# covox.net
KiCad netlist of a schematic drawn in EAGLE
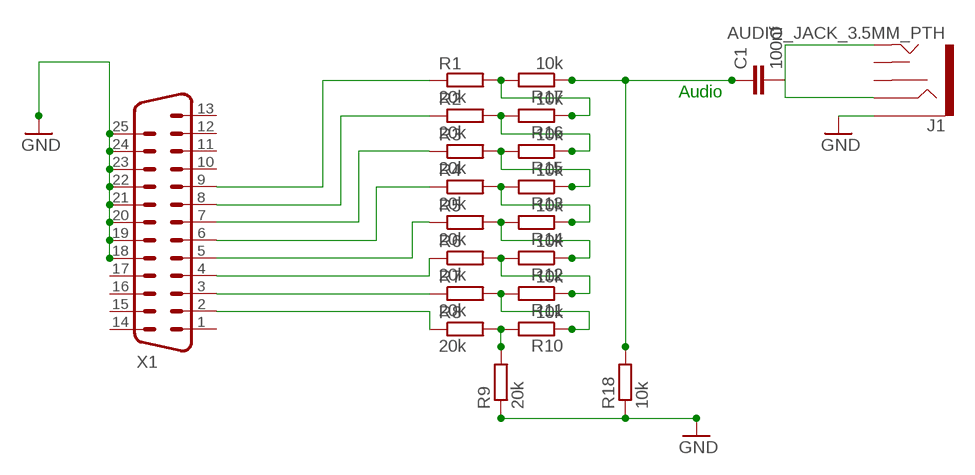
[diagram p0: schematic, sheet 1]

(export (version "E")
  (design (tool "Eeschema 10.0.6"))
  (components
    (comp (ref "C1")
      (value "100nf")
      (footprint "eagle-import:C2.5-2")
      (libsource (lib "eagle-import") (part "C2.5/2"))
    )
    (comp (ref "J1")
      (value "AUDIO_JACK_3.5MM_PTH")
      (footprint "eagle-import:AUDIO-JACK")
      (libsource (lib "eagle-import") (part "AUDIO_JACK_3.5MM_PTH"))
    )
    (comp (ref "R1")
      (value "20k")
      (footprint "eagle-import:0204_7")
      (libsource (lib "eagle-import") (part "R-EU_0204/7"))
    )
    (comp (ref "R2")
      (value "20k")
      (footprint "eagle-import:0204_7")
      (libsource (lib "eagle-import") (part "R-EU_0204/7"))
    )
    (comp (ref "R3")
      (value "20k")
      (footprint "eagle-import:0204_7")
      (libsource (lib "eagle-import") (part "R-EU_0204/7"))
    )
    (comp (ref "R4")
      (value "20k")
      (footprint "eagle-import:0204_7")
      (libsource (lib "eagle-import") (part "R-EU_0204/7"))
    )
    (comp (ref "R5")
      (value "20k")
      (footprint "eagle-import:0204_7")
      (libsource (lib "eagle-import") (part "R-EU_0204/7"))
    )
    (comp (ref "R6")
      (value "20k")
      (footprint "eagle-import:0204_7")
      (libsource (lib "eagle-import") (part "R-EU_0204/7"))
    )
    (comp (ref "R7")
      (value "20k")
      (footprint "eagle-import:0204_7")
      (libsource (lib "eagle-import") (part "R-EU_0204/7"))
    )
    (comp (ref "R8")
      (value "20k")
      (footprint "eagle-import:0204_7")
      (libsource (lib "eagle-import") (part "R-EU_0204/7"))
    )
    (comp (ref "R9")
      (value "20k")
      (footprint "eagle-import:0204_7")
      (libsource (lib "eagle-import") (part "R-EU_0204/7"))
    )
    (comp (ref "R10")
      (value "10k")
      (footprint "eagle-import:0204_7")
      (libsource (lib "eagle-import") (part "R-EU_0204/7"))
    )
    (comp (ref "R11")
      (value "10k")
      (footprint "eagle-import:0204_7")
      (libsource (lib "eagle-import") (part "R-EU_0204/7"))
    )
    (comp (ref "R12")
      (value "10k")
      (footprint "eagle-import:0204_7")
      (libsource (lib "eagle-import") (part "R-EU_0204/7"))
    )
    (comp (ref "R13")
      (value "10k")
      (footprint "eagle-import:0204_7")
      (libsource (lib "eagle-import") (part "R-EU_0204/7"))
    )
    (comp (ref "R14")
      (value "10k")
      (footprint "eagle-import:0204_7")
      (libsource (lib "eagle-import") (part "R-EU_0204/7"))
    )
    (comp (ref "R15")
      (value "10k")
      (footprint "eagle-import:0204_7")
      (libsource (lib "eagle-import") (part "R-EU_0204/7"))
    )
    (comp (ref "R16")
      (value "10k")
      (footprint "eagle-import:0204_7")
      (libsource (lib "eagle-import") (part "R-EU_0204/7"))
    )
    (comp (ref "R17")
      (value "10k")
      (footprint "eagle-import:0204_7")
      (libsource (lib "eagle-import") (part "R-EU_0204/7"))
    )
    (comp (ref "R18")
      (value "10k")
      (footprint "eagle-import:0204_7")
      (libsource (lib "eagle-import") (part "R-EU_0204/7"))
    )
    (comp (ref "X1")
      (value "M25HP")
      (footprint "eagle-import:M25HP")
      (libsource (lib "eagle-import") (part "M25HP"))
    )
  )
  (nets
    (net (code "1") (name "GND") (class "Default")
      (node (ref "J1") (pin "SLEEVE") (pinfunction "SLEEVE_SLEEVE") (pintype "bidirectional"))
      (node (ref "R18") (pin "1") (pinfunction "1_1") (pintype "passive"))
      (node (ref "R9") (pin "1") (pinfunction "1_1") (pintype "passive"))
      (node (ref "X1") (pin "18") (pinfunction "18_18") (pintype "passive"))
      (node (ref "X1") (pin "19") (pinfunction "19_19") (pintype "passive"))
      (node (ref "X1") (pin "20") (pinfunction "20_20") (pintype "passive"))
      (node (ref "X1") (pin "21") (pinfunction "21_21") (pintype "passive"))
      (node (ref "X1") (pin "22") (pinfunction "22_22") (pintype "passive"))
      (node (ref "X1") (pin "23") (pinfunction "23_23") (pintype "passive"))
      (node (ref "X1") (pin "24") (pinfunction "24_24") (pintype "passive"))
      (node (ref "X1") (pin "25") (pinfunction "25_25") (pintype "passive"))
    )
    (net (code "2") (name "Net-(C1-Pad1)") (class "Default")
      (node (ref "C1") (pin "1") (pinfunction "1_1") (pintype "passive"))
      (node (ref "R17") (pin "1") (pinfunction "1_1") (pintype "passive"))
      (node (ref "R18") (pin "2") (pinfunction "2_2") (pintype "passive"))
    )
    (net (code "3") (name "Net-(C1-Pad2)") (class "Default")
      (node (ref "C1") (pin "2") (pinfunction "2_2") (pintype "passive"))
      (node (ref "J1") (pin "RING") (pinfunction "RING_RING") (pintype "bidirectional"))
      (node (ref "J1") (pin "TIP") (pinfunction "TIP_TIP") (pintype "bidirectional"))
    )
    (net (code "4") (name "Net-(R1-Pad1)") (class "Default")
      (node (ref "R1") (pin "1") (pinfunction "1_1") (pintype "passive"))
      (node (ref "X1") (pin "9") (pinfunction "9_9") (pintype "passive"))
    )
    (net (code "5") (name "Net-(R1-Pad2)") (class "Default")
      (node (ref "R1") (pin "2") (pinfunction "2_2") (pintype "passive"))
      (node (ref "R16") (pin "1") (pinfunction "1_1") (pintype "passive"))
      (node (ref "R17") (pin "2") (pinfunction "2_2") (pintype "passive"))
    )
    (net (code "6") (name "Net-(R2-Pad1)") (class "Default")
      (node (ref "R2") (pin "1") (pinfunction "1_1") (pintype "passive"))
      (node (ref "X1") (pin "8") (pinfunction "8_8") (pintype "passive"))
    )
    (net (code "7") (name "Net-(R3-Pad1)") (class "Default")
      (node (ref "R3") (pin "1") (pinfunction "1_1") (pintype "passive"))
      (node (ref "X1") (pin "7") (pinfunction "7_7") (pintype "passive"))
    )
    (net (code "8") (name "Net-(R4-Pad1)") (class "Default")
      (node (ref "R4") (pin "1") (pinfunction "1_1") (pintype "passive"))
      (node (ref "X1") (pin "6") (pinfunction "6_6") (pintype "passive"))
    )
    (net (code "9") (name "Net-(R5-Pad1)") (class "Default")
      (node (ref "R5") (pin "1") (pinfunction "1_1") (pintype "passive"))
      (node (ref "X1") (pin "5") (pinfunction "5_5") (pintype "passive"))
    )
    (net (code "10") (name "Net-(R6-Pad1)") (class "Default")
      (node (ref "R6") (pin "1") (pinfunction "1_1") (pintype "passive"))
      (node (ref "X1") (pin "4") (pinfunction "4_4") (pintype "passive"))
    )
    (net (code "11") (name "Net-(R7-Pad1)") (class "Default")
      (node (ref "R7") (pin "1") (pinfunction "1_1") (pintype "passive"))
      (node (ref "X1") (pin "3") (pinfunction "3_3") (pintype "passive"))
    )
    (net (code "12") (name "Net-(R8-Pad1)") (class "Default")
      (node (ref "R8") (pin "1") (pinfunction "1_1") (pintype "passive"))
      (node (ref "X1") (pin "2") (pinfunction "2_2") (pintype "passive"))
    )
    (net (code "13") (name "Net-(R10-Pad1)") (class "Default")
      (node (ref "R10") (pin "1") (pinfunction "1_1") (pintype "passive"))
      (node (ref "R11") (pin "2") (pinfunction "2_2") (pintype "passive"))
      (node (ref "R7") (pin "2") (pinfunction "2_2") (pintype "passive"))
    )
    (net (code "14") (name "Net-(R10-Pad2)") (class "Default")
      (node (ref "R10") (pin "2") (pinfunction "2_2") (pintype "passive"))
      (node (ref "R8") (pin "2") (pinfunction "2_2") (pintype "passive"))
      (node (ref "R9") (pin "2") (pinfunction "2_2") (pintype "passive"))
    )
    (net (code "15") (name "Net-(R11-Pad1)") (class "Default")
      (node (ref "R11") (pin "1") (pinfunction "1_1") (pintype "passive"))
      (node (ref "R12") (pin "2") (pinfunction "2_2") (pintype "passive"))
      (node (ref "R6") (pin "2") (pinfunction "2_2") (pintype "passive"))
    )
    (net (code "16") (name "Net-(R12-Pad1)") (class "Default")
      (node (ref "R12") (pin "1") (pinfunction "1_1") (pintype "passive"))
      (node (ref "R14") (pin "2") (pinfunction "2_2") (pintype "passive"))
      (node (ref "R5") (pin "2") (pinfunction "2_2") (pintype "passive"))
    )
    (net (code "17") (name "Net-(R13-Pad1)") (class "Default")
      (node (ref "R13") (pin "1") (pinfunction "1_1") (pintype "passive"))
      (node (ref "R15") (pin "2") (pinfunction "2_2") (pintype "passive"))
      (node (ref "R3") (pin "2") (pinfunction "2_2") (pintype "passive"))
    )
    (net (code "18") (name "Net-(R13-Pad2)") (class "Default")
      (node (ref "R13") (pin "2") (pinfunction "2_2") (pintype "passive"))
      (node (ref "R14") (pin "1") (pinfunction "1_1") (pintype "passive"))
      (node (ref "R4") (pin "2") (pinfunction "2_2") (pintype "passive"))
    )
    (net (code "19") (name "Net-(R15-Pad1)") (class "Default")
      (node (ref "R15") (pin "1") (pinfunction "1_1") (pintype "passive"))
      (node (ref "R16") (pin "2") (pinfunction "2_2") (pintype "passive"))
      (node (ref "R2") (pin "2") (pinfunction "2_2") (pintype "passive"))
    )
    (net (code "20") (name "unconnected-(J1-PadRSH)") (class "Default")
      (node (ref "J1") (pin "RSH") (pinfunction "RSH_RSH") (pintype "bidirectional"))
    )
    (net (code "21") (name "unconnected-(J1-PadTSH)") (class "Default")
      (node (ref "J1") (pin "TSH") (pinfunction "TSH_TSH") (pintype "bidirectional"))
    )
    (net (code "22") (name "unconnected-(X1-Pad1)") (class "Default")
      (node (ref "X1") (pin "1") (pinfunction "1_1") (pintype "passive"))
    )
    (net (code "23") (name "unconnected-(X1-Pad10)") (class "Default")
      (node (ref "X1") (pin "10") (pinfunction "10_10") (pintype "passive"))
    )
    (net (code "24") (name "unconnected-(X1-Pad11)") (class "Default")
      (node (ref "X1") (pin "11") (pinfunction "11_11") (pintype "passive"))
    )
    (net (code "25") (name "unconnected-(X1-Pad12)") (class "Default")
      (node (ref "X1") (pin "12") (pinfunction "12_12") (pintype "passive"))
    )
    (net (code "26") (name "unconnected-(X1-Pad13)") (class "Default")
      (node (ref "X1") (pin "13") (pinfunction "13_13") (pintype "passive"))
    )
    (net (code "27") (name "unconnected-(X1-Pad14)") (class "Default")
      (node (ref "X1") (pin "14") (pinfunction "14_14") (pintype "passive"))
    )
    (net (code "28") (name "unconnected-(X1-Pad15)") (class "Default")
      (node (ref "X1") (pin "15") (pinfunction "15_15") (pintype "passive"))
    )
    (net (code "29") (name "unconnected-(X1-Pad16)") (class "Default")
      (node (ref "X1") (pin "16") (pinfunction "16_16") (pintype "passive"))
    )
    (net (code "30") (name "unconnected-(X1-Pad17)") (class "Default")
      (node (ref "X1") (pin "17") (pinfunction "17_17") (pintype "passive"))
    )
  )
)
